# Regulated_voltage_input_source.net
KiCad netlist of a schematic drawn in Altium Designer
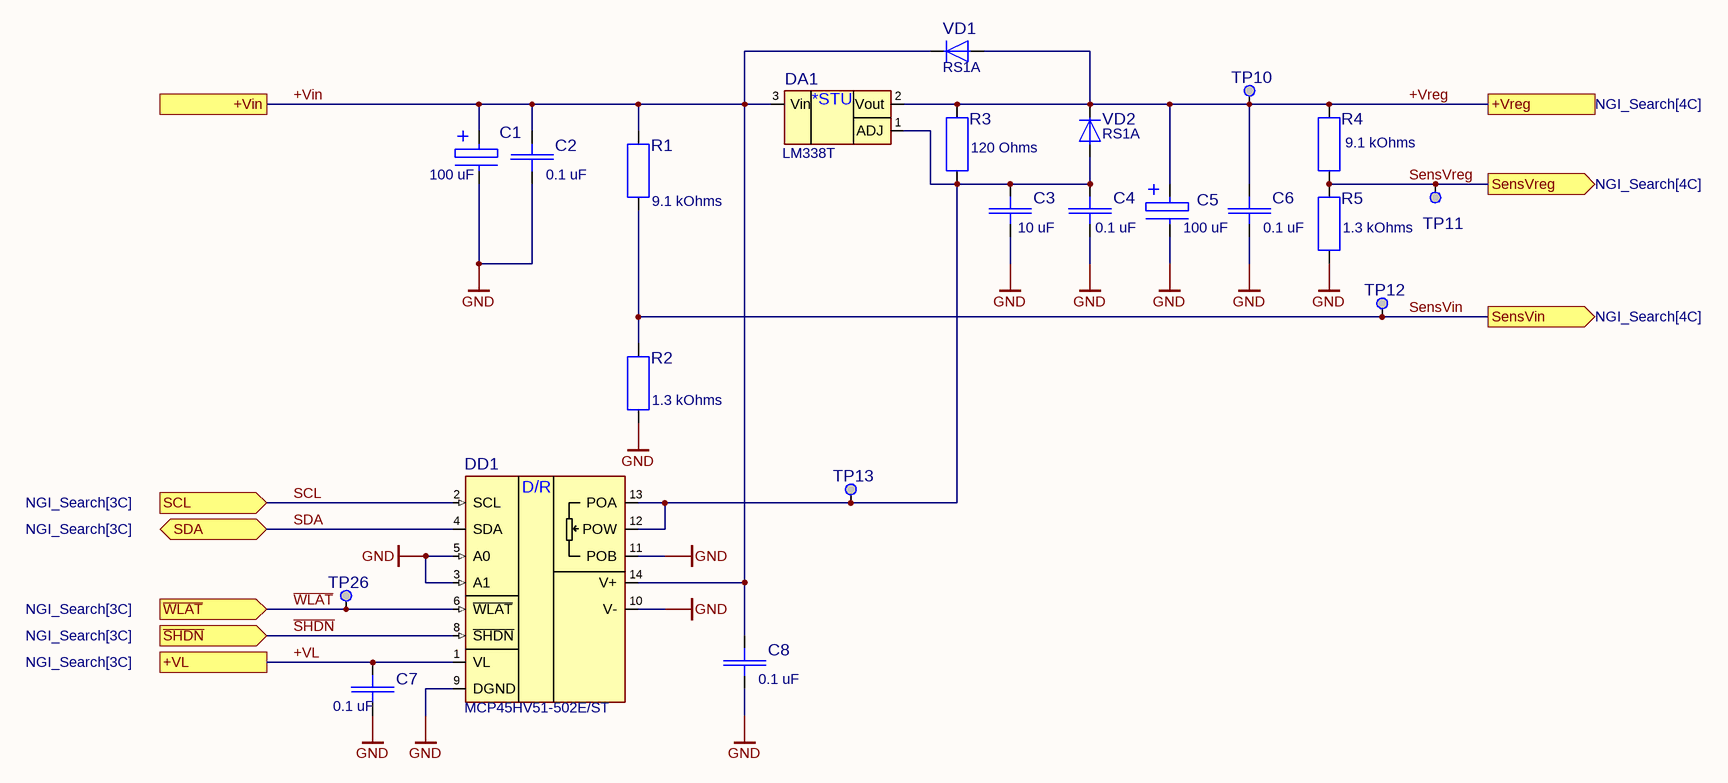
[diagram p0: Regulated voltage input source.SchDoc]

(export (version "E")
  (design (tool "Eeschema 10.0.6"))
  (components
    (comp (ref "C1")
      (value "100 uF")
      (footprint "EEH-ZA1V101P")
      (description "Aluminium Organic Polymer Capacitors 35VDC 100uF 20% AEC-Q200")
      (fields (field (name "MANUFACTURERPARTNUMBER") "EEH-ZA1V101P") (field (name "TOLERANCE") "20%"))
      (libsource (lib "NGI_Search") (part "EEH-ZA1V101P"))
    )
    (comp (ref "C2")
      (value "0.1 uF")
      (footprint "Capacitor0805_THICKNESS0.8")
      (description "Multilayer Ceramic Capacitors MLCC - SMD/SMT 100nF+/-10% 50V X7R 0805")
      (fields (field (name "TOLERANCE") "10%") (field (name "MANUFACTURERPARTNUMBER") "CL21B104KBCNNWC"))
      (libsource (lib "NGI_Search") (part "CL21B104KBCNNWC"))
    )
    (comp (ref "C3")
      (value "10 uF")
      (footprint "Capacitor0805_THICKNESS1.45")
      (description "Multilayer Ceramic Capacitors MLCC - SMD/SMT 10 uF 35 VDC 10% 0805 X5R")
      (fields (field (name "TOLERANCE") "10%") (field (name "MANUFACTURERPARTNUMBER") "GRM21BR6YA106KE43K"))
      (libsource (lib "NGI_Search") (part "GRM21BR6YA106KE43K"))
    )
    (comp (ref "C4")
      (value "0.1 uF")
      (footprint "Capacitor0805_THICKNESS0.8")
      (description "Multilayer Ceramic Capacitors MLCC - SMD/SMT 100nF+/-10% 50V X7R 0805")
      (fields (field (name "TOLERANCE") "10%") (field (name "MANUFACTURERPARTNUMBER") "CL21B104KBCNNWC"))
      (libsource (lib "NGI_Search") (part "CL21B104KBCNNWC"))
    )
    (comp (ref "C5")
      (value "100 uF")
      (footprint "EEH-ZA1V101P")
      (description "Aluminium Organic Polymer Capacitors 35VDC 100uF 20% AEC-Q200")
      (fields (field (name "MANUFACTURERPARTNUMBER") "EEH-ZA1V101P") (field (name "TOLERANCE") "20%"))
      (libsource (lib "NGI_Search") (part "EEH-ZA1V101P"))
    )
    (comp (ref "C6")
      (value "0.1 uF")
      (footprint "Capacitor0805_THICKNESS0.8")
      (description "Multilayer Ceramic Capacitors MLCC - SMD/SMT 100nF+/-10% 50V X7R 0805")
      (fields (field (name "TOLERANCE") "10%") (field (name "MANUFACTURERPARTNUMBER") "CL21B104KBCNNWC"))
      (libsource (lib "NGI_Search") (part "CL21B104KBCNNWC"))
    )
    (comp (ref "C7")
      (value "0.1 uF")
      (footprint "Capacitor0805_THICKNESS0.8")
      (description "Multilayer Ceramic Capacitors MLCC - SMD/SMT 100nF+/-10% 50V X7R 0805")
      (fields (field (name "TOLERANCE") "10%") (field (name "MANUFACTURERPARTNUMBER") "CL21B104KBCNNWC"))
      (libsource (lib "NGI_Search") (part "CL21B104KBCNNWC"))
    )
    (comp (ref "C8")
      (value "0.1 uF")
      (footprint "Capacitor0805_THICKNESS0.8")
      (description "Multilayer Ceramic Capacitors MLCC - SMD/SMT 100nF+/-10% 50V X7R 0805")
      (fields (field (name "TOLERANCE") "10%") (field (name "MANUFACTURERPARTNUMBER") "CL21B104KBCNNWC"))
      (libsource (lib "NGI_Search") (part "CL21B104KBCNNWC"))
    )
    (comp (ref "DA1")
      (value "LM338T")
      (footprint "LM338T TO-220 with HS FA-T220-64E")
      (description "Linear Voltage Regulators 5 AMP ADJUSTABLE REG")
      (fields
        (field (name "MANUFACTURER") "Texas Instruments")
        (field (name "MOUSER PART NUMBER") "926-LM338T/NOPB")
      )
      (libsource (lib "NGI_Search") (part "LM338T"))
    )
    (comp (ref "DD1")
      (value "MCP45HV51-502E/ST")
      (footprint "TSOP-14")
      (description "Digital Potentiometer ICs 8-bit, vol Digi Pot 5K ohm, 14ld TSSOP")
      (fields
        (field (name "MANUFACTURER") "Microchip")
        (field (name "MOUSER PART NUMBER") "579-MCP45HV51-502EST")
      )
      (libsource (lib "NGI_Search") (part "MCP45HV51-502E/ST"))
    )
    (comp (ref "R1")
      (value "9.1 kOhms")
      (footprint "Resistor0805_THICKNESS0.6")
      (description "Thick Film Resistors 9.1 kOhms 125 mW 0805 1%")
      (fields (field (name "MANUFACTURERPARTNUMBER") "RC0805FR-079K1L") (field (name "TOLERANCE") "1%"))
      (libsource (lib "NGI_Search") (part "RC0805FR-079K1L"))
    )
    (comp (ref "R2")
      (value "1.3 kOhms")
      (footprint "Resistor0805_THICKNESS0.6")
      (description "Thick Film Resistors 1.3 kOhms 250 mW 0805 1%")
      (fields (field (name "MANUFACTURERPARTNUMBER") "RC0805FR-101K3") (field (name "TOLERANCE") "1%"))
      (libsource (lib "NGI_Search") (part "RC0805FR-101K3L"))
    )
    (comp (ref "R3")
      (value "120 Ohms")
      (footprint "Resistor0805_THICKNESS0.6")
      (description "Thick Film Resistors 120 Ohms 125 mW 0805 1%")
      (fields (field (name "MANUFACTURERPARTNUMBER") "RC0805FR-07120RL") (field (name "TOLERANCE") "1%"))
      (libsource (lib "NGI_Search") (part "RC0805FR-07120RL"))
    )
    (comp (ref "R4")
      (value "9.1 kOhms")
      (footprint "Resistor0805_THICKNESS0.6")
      (description "Thick Film Resistors 9.1 kOhms 125 mW 0805 1%")
      (fields (field (name "MANUFACTURERPARTNUMBER") "RC0805FR-079K1L") (field (name "TOLERANCE") "1%"))
      (libsource (lib "NGI_Search") (part "RC0805FR-079K1L"))
    )
    (comp (ref "R5")
      (value "1.3 kOhms")
      (footprint "Resistor0805_THICKNESS0.6")
      (description "Thick Film Resistors 1.3 kOhms 250 mW 0805 1%")
      (fields (field (name "MANUFACTURERPARTNUMBER") "RC0805FR-101K3") (field (name "TOLERANCE") "1%"))
      (libsource (lib "NGI_Search") (part "RC0805FR-101K3L"))
    )
    (comp (ref "TP10")
      (value "test point")
      (footprint "test point")
      (libsource (lib "NGI_Search") (part "test point"))
    )
    (comp (ref "TP11")
      (value "test point")
      (footprint "test point")
      (libsource (lib "NGI_Search") (part "test point"))
    )
    (comp (ref "TP12")
      (value "test point")
      (footprint "test point")
      (libsource (lib "NGI_Search") (part "test point"))
    )
    (comp (ref "TP13")
      (value "test point")
      (footprint "test point")
      (libsource (lib "NGI_Search") (part "test point"))
    )
    (comp (ref "TP26")
      (value "test point")
      (footprint "test point")
      (libsource (lib "NGI_Search") (part "test point"))
    )
    (comp (ref "VD1")
      (value "RS1A")
      (footprint "RS1A_CASE_SMA 403AE")
      (description "Rectifiers 50V 1a Fast Rect SMa")
      (fields (field (name "MANUFACTURER") "onsemi") (field (name "MOUSER PART NUMBER") "512-RS1A"))
      (libsource (lib "NGI_Search") (part "RS1A"))
    )
    (comp (ref "VD2")
      (value "RS1A")
      (footprint "RS1A_CASE_SMA 403AE")
      (description "Rectifiers 50V 1a Fast Rect SMa")
      (fields (field (name "MANUFACTURER") "onsemi") (field (name "MOUSER PART NUMBER") "512-RS1A"))
      (libsource (lib "NGI_Search") (part "RS1A"))
    )
  )
  (nets
    (net (code "1") (name "/+VL") (class "Default")
      (node (ref "C7") (pin "2") (pinfunction "2_2") (pintype "passive"))
      (node (ref "DD1") (pin "1") (pinfunction "VL_1") (pintype "power_in"))
    )
    (net (code "2") (name "/+Vin") (class "Default")
      (node (ref "C1") (pin "1") (pinfunction "1_1") (pintype "passive"))
      (node (ref "C2") (pin "1") (pinfunction "1_1") (pintype "passive"))
      (node (ref "C8") (pin "2") (pinfunction "2_2") (pintype "passive"))
      (node (ref "DA1") (pin "3") (pinfunction "Vin_3") (pintype "power_in"))
      (node (ref "DD1") (pin "14") (pinfunction "V+_14") (pintype "power_in"))
      (node (ref "R1") (pin "1") (pinfunction "1_1") (pintype "passive"))
      (node (ref "VD1") (pin "C") (pinfunction "C_C") (pintype "passive"))
    )
    (net (code "3") (name "/+Vreg") (class "Default")
      (node (ref "C5") (pin "1") (pinfunction "1_1") (pintype "passive"))
      (node (ref "C6") (pin "2") (pinfunction "2_2") (pintype "passive"))
      (node (ref "DA1") (pin "2") (pinfunction "Vout_2") (pintype "power_in"))
      (node (ref "R3") (pin "2") (pinfunction "2_2") (pintype "passive"))
      (node (ref "R4") (pin "1") (pinfunction "1_1") (pintype "passive"))
      (node (ref "TP10") (pin "1") (pinfunction "1_1") (pintype "passive"))
      (node (ref "VD1") (pin "A") (pinfunction "A_A") (pintype "passive"))
      (node (ref "VD2") (pin "C") (pinfunction "C_C") (pintype "passive"))
    )
    (net (code "4") (name "/SCL") (class "Default")
      (node (ref "DD1") (pin "2") (pinfunction "SCL_2") (pintype "input"))
    )
    (net (code "5") (name "/SDA") (class "Default")
      (node (ref "DD1") (pin "4") (pinfunction "SDA_4") (pintype "bidirectional"))
    )
    (net (code "6") (name "/SensVin") (class "Default")
      (node (ref "R1") (pin "2") (pinfunction "2_2") (pintype "passive"))
      (node (ref "R2") (pin "1") (pinfunction "1_1") (pintype "passive"))
      (node (ref "TP12") (pin "1") (pinfunction "1_1") (pintype "passive"))
    )
    (net (code "7") (name "/SensVreg") (class "Default")
      (node (ref "R4") (pin "2") (pinfunction "2_2") (pintype "passive"))
      (node (ref "R5") (pin "1") (pinfunction "1_1") (pintype "passive"))
      (node (ref "TP11") (pin "1") (pinfunction "1_1") (pintype "passive"))
    )
    (net (code "8") (name "/~{SHDN}") (class "Default")
      (node (ref "DD1") (pin "8") (pinfunction "~{SHDN}_8") (pintype "input"))
    )
    (net (code "9") (name "/~{WLAT}") (class "Default")
      (node (ref "DD1") (pin "6") (pinfunction "~{WLAT}_6") (pintype "input"))
      (node (ref "TP26") (pin "1") (pinfunction "1_1") (pintype "passive"))
    )
    (net (code "10") (name "GND") (class "Default")
      (node (ref "C1") (pin "2") (pinfunction "2_2") (pintype "passive"))
      (node (ref "C2") (pin "2") (pinfunction "2_2") (pintype "passive"))
      (node (ref "C3") (pin "1") (pinfunction "1_1") (pintype "passive"))
      (node (ref "C4") (pin "1") (pinfunction "1_1") (pintype "passive"))
      (node (ref "C5") (pin "2") (pinfunction "2_2") (pintype "passive"))
      (node (ref "C6") (pin "1") (pinfunction "1_1") (pintype "passive"))
      (node (ref "C7") (pin "1") (pinfunction "1_1") (pintype "passive"))
      (node (ref "C8") (pin "1") (pinfunction "1_1") (pintype "passive"))
      (node (ref "DD1") (pin "10") (pinfunction "V-_10") (pintype "power_in"))
      (node (ref "DD1") (pin "11") (pinfunction "POB_11") (pintype "passive"))
      (node (ref "DD1") (pin "3") (pinfunction "A1_3") (pintype "input"))
      (node (ref "DD1") (pin "5") (pinfunction "A0_5") (pintype "input"))
      (node (ref "DD1") (pin "9") (pinfunction "DGND_9") (pintype "power_in"))
      (node (ref "R2") (pin "2") (pinfunction "2_2") (pintype "passive"))
      (node (ref "R5") (pin "2") (pinfunction "2_2") (pintype "passive"))
    )
    (net (code "11") (name "Net-(DA1-ADJ)") (class "Default")
      (node (ref "C3") (pin "2") (pinfunction "2_2") (pintype "passive"))
      (node (ref "C4") (pin "2") (pinfunction "2_2") (pintype "passive"))
      (node (ref "DA1") (pin "1") (pinfunction "ADJ_1") (pintype "passive"))
      (node (ref "DD1") (pin "12") (pinfunction "POW_12") (pintype "passive"))
      (node (ref "DD1") (pin "13") (pinfunction "POA_13") (pintype "passive"))
      (node (ref "R3") (pin "1") (pinfunction "1_1") (pintype "passive"))
      (node (ref "TP13") (pin "1") (pinfunction "1_1") (pintype "passive"))
      (node (ref "VD2") (pin "A") (pinfunction "A_A") (pintype "passive"))
    )
    (net (code "12") (name "unconnected-(DD1-NC-Pad7)") (class "Default")
      (node (ref "DD1") (pin "7") (pinfunction "NC_7") (pintype "passive"))
    )
  )
)
